# Accelerometer.net
KiCad netlist of a schematic drawn in Altium Designer
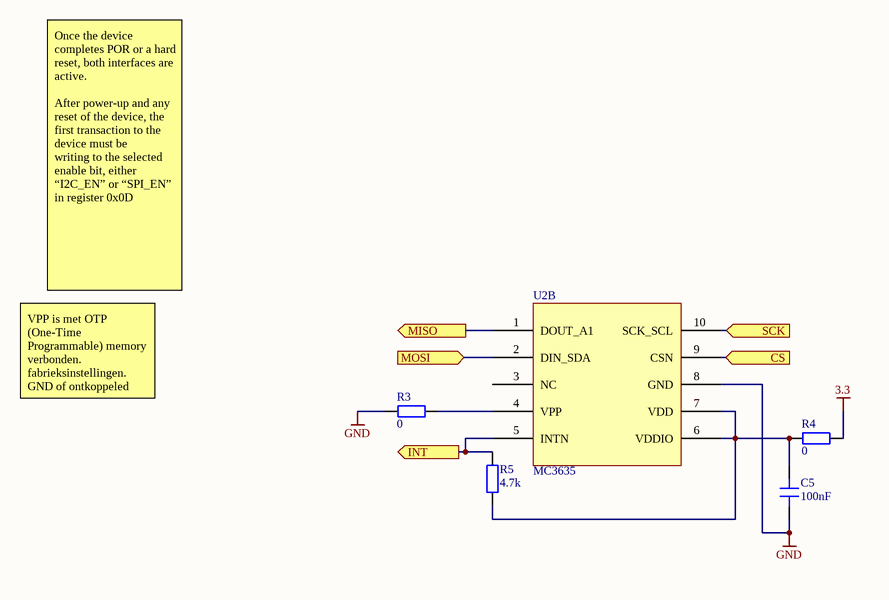
[diagram p0: Accelerometer.SchDoc]

(export (version "E")
  (design (tool "Eeschema 10.0.6"))
  (components
    (comp (ref "C5") (value "100nF") (footprint "0603_CAP") (libsource (lib "passive_components") (part "C")))
    (comp (ref "R3") (value "0") (footprint "0603") (libsource (lib "passive_components") (part "R")))
    (comp (ref "R4") (value "0") (footprint "0603") (libsource (lib "passive_components") (part "R")))
    (comp (ref "R5") (value "4.7k") (footprint "0402_RES") (libsource (lib "passive_components") (part "R")))
    (comp (ref "U2") (value "MC3635") (footprint "MC3635") (libsource (lib "MC3635") (part "MC3635")))
  )
  (nets
    (net (code "1") (name "/CS") (class "Default")
      (node (ref "U2") (pin "9") (pinfunction "CSN_9") (pintype "passive"))
    )
    (net (code "2") (name "/INT") (class "Default")
      (node (ref "R5") (pin "2") (pinfunction "26_2") (pintype "passive"))
      (node (ref "U2") (pin "5") (pinfunction "INTN_5") (pintype "passive"))
    )
    (net (code "3") (name "/MISO") (class "Default")
      (node (ref "U2") (pin "1") (pinfunction "DOUT_A1_1") (pintype "passive"))
    )
    (net (code "4") (name "/MOSI") (class "Default")
      (node (ref "U2") (pin "2") (pinfunction "DIN_SDA_2") (pintype "passive"))
    )
    (net (code "5") (name "/SCK") (class "Default")
      (node (ref "U2") (pin "10") (pinfunction "SCK_SCL_10") (pintype "passive"))
    )
    (net (code "6") (name "3.3") (class "Default")
      (node (ref "R4") (pin "1") (pinfunction "25_1") (pintype "passive"))
    )
    (net (code "7") (name "GND") (class "Default")
      (node (ref "C5") (pin "1") (pinfunction "1_1") (pintype "passive"))
      (node (ref "R3") (pin "2") (pinfunction "26_2") (pintype "passive"))
      (node (ref "U2") (pin "8") (pinfunction "GND_8") (pintype "passive"))
    )
    (net (code "8") (name "Net-(C5-28)") (class "Default")
      (node (ref "C5") (pin "2") (pinfunction "28_2") (pintype "passive"))
      (node (ref "R4") (pin "2") (pinfunction "26_2") (pintype "passive"))
      (node (ref "R5") (pin "1") (pinfunction "25_1") (pintype "passive"))
      (node (ref "U2") (pin "6") (pinfunction "VDDIO_6") (pintype "passive"))
      (node (ref "U2") (pin "7") (pinfunction "VDD_7") (pintype "passive"))
    )
    (net (code "9") (name "Net-(R3-25)") (class "Default")
      (node (ref "R3") (pin "1") (pinfunction "25_1") (pintype "passive"))
      (node (ref "U2") (pin "4") (pinfunction "VPP_4") (pintype "passive"))
    )
    (net (code "10") (name "unconnected-(U2B-NC-Pad3)") (class "Default")
      (node (ref "U2") (pin "3") (pinfunction "NC_3") (pintype "passive"))
    )
  )
)
